# binaryspacebadgev1.net
KiCad netlist of a schematic drawn in EAGLE
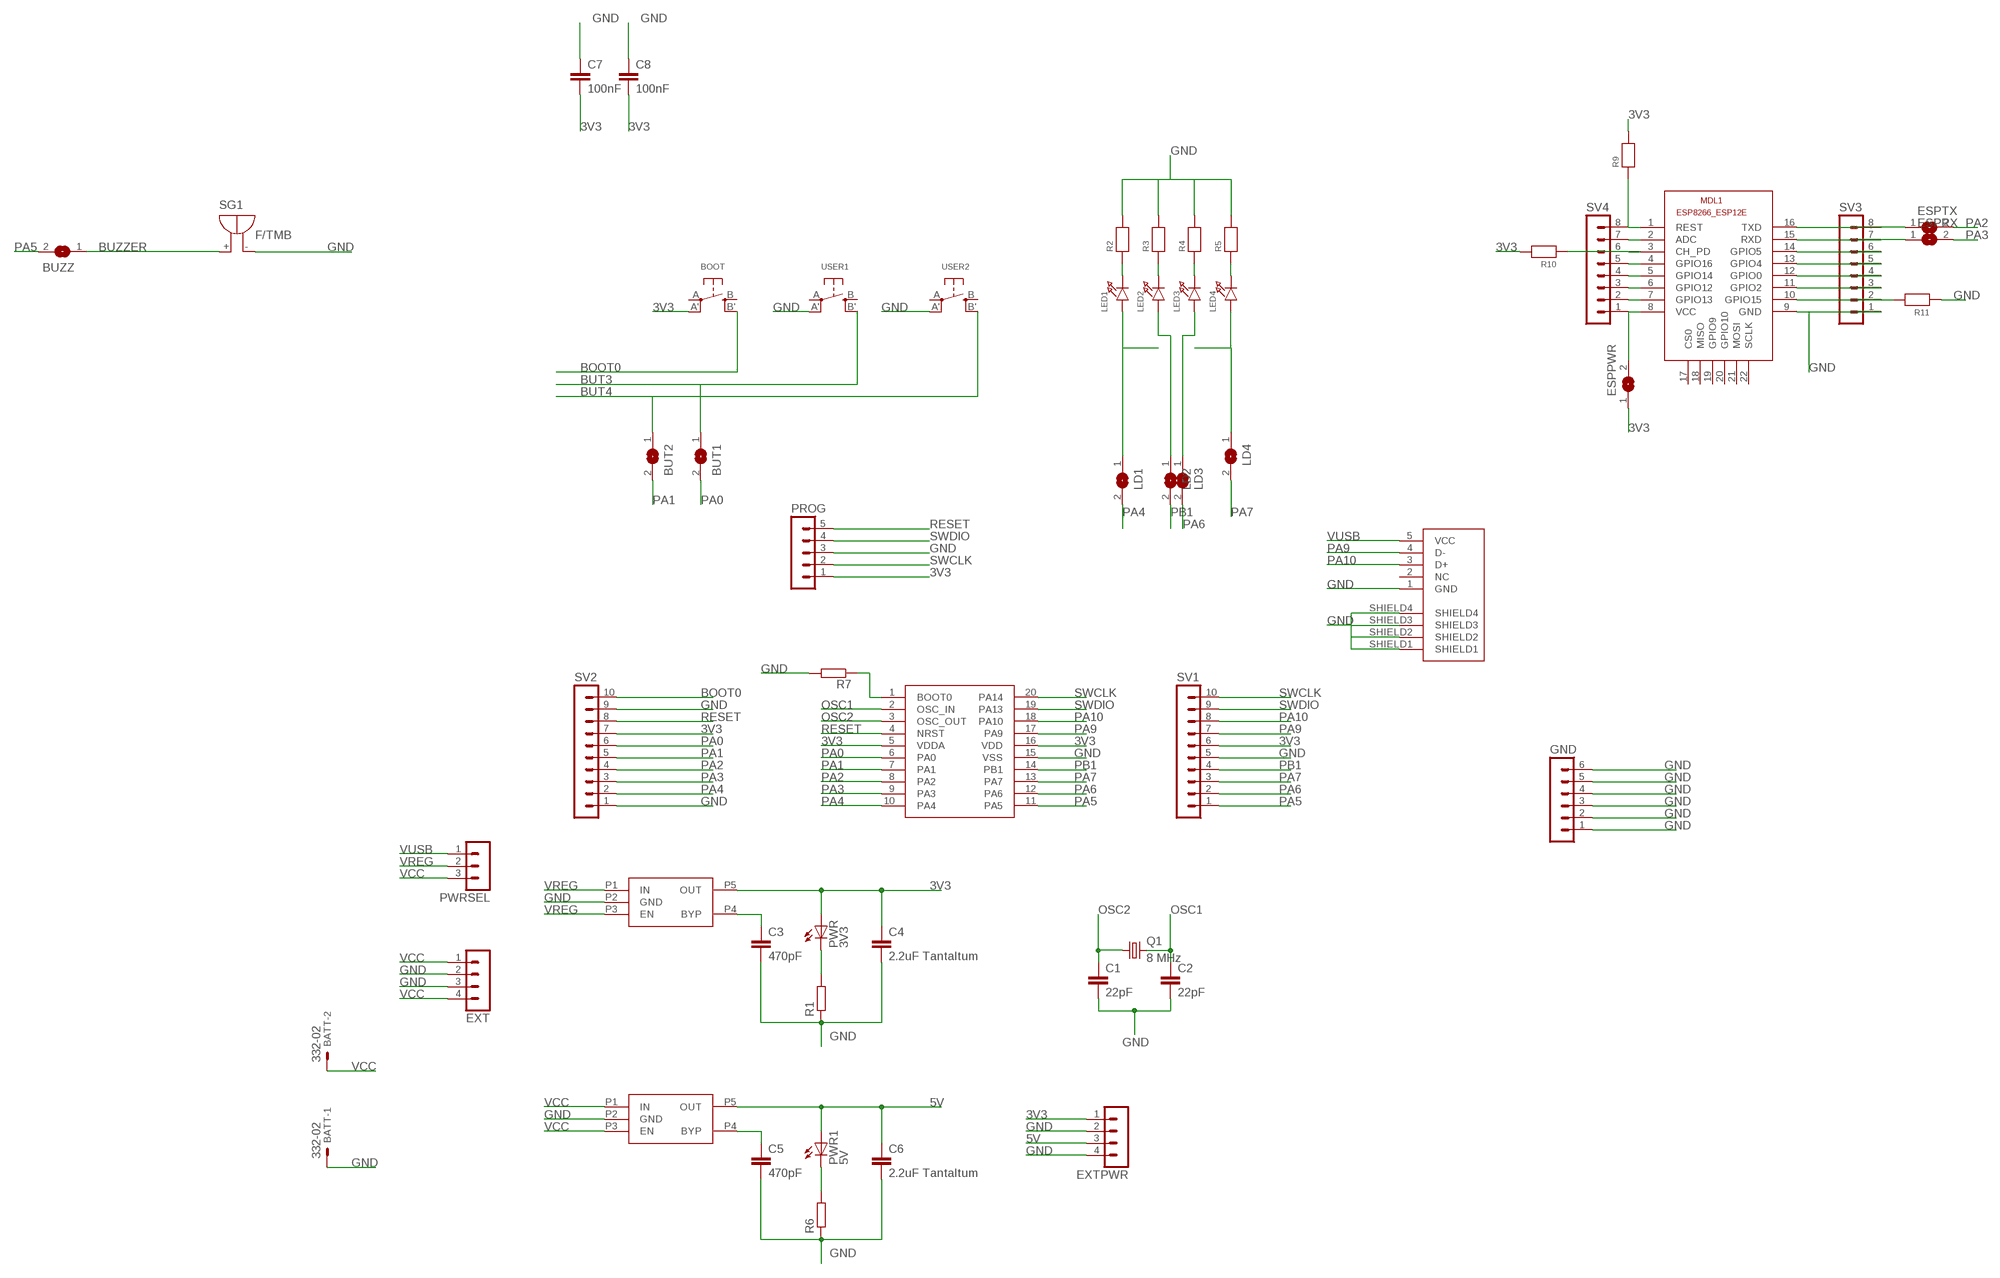
[diagram p0: schematic, sheet 1]

(export (version "E")
  (design (tool "Eeschema 10.0.6"))
  (components
    (comp (ref "BATT")
      (value "332-02")
      (footprint "eagle-import:332-02")
      (libsource (lib "eagle-import") (part "332-02"))
    )
    (comp (ref "BOOT")
      (value "SWITCH_TACT_SMT")
      (footprint "eagle-import:EVQ-Q2")
      (libsource (lib "eagle-import") (part "SWITCH_TACT_SMT"))
    )
    (comp (ref "BUT1")
      (value "SOLDERJUMPER")
      (footprint "eagle-import:SOLDERJUMPER_ARROW_NOPASTE")
      (libsource (lib "eagle-import") (part "SOLDERJUMPER"))
    )
    (comp (ref "BUT2")
      (value "SOLDERJUMPER")
      (footprint "eagle-import:SOLDERJUMPER_ARROW_NOPASTE")
      (libsource (lib "eagle-import") (part "SOLDERJUMPER"))
    )
    (comp (ref "BUZZ")
      (value "SOLDERJUMPER")
      (footprint "eagle-import:SOLDERJUMPER_ARROW_NOPASTE")
      (libsource (lib "eagle-import") (part "SOLDERJUMPER"))
    )
    (comp (ref "C1")
      (value "22pF")
      (footprint "eagle-import:C0603")
      (libsource (lib "eagle-import") (part "C-EUC0603"))
    )
    (comp (ref "C2")
      (value "22pF")
      (footprint "eagle-import:C0603")
      (libsource (lib "eagle-import") (part "C-EUC0603"))
    )
    (comp (ref "C3")
      (value "470pF")
      (footprint "eagle-import:C0603")
      (libsource (lib "eagle-import") (part "C-EUC0603"))
    )
    (comp (ref "C4")
      (value "2.2uF Tantaltum")
      (footprint "eagle-import:C0805")
      (libsource (lib "eagle-import") (part "C-EUC0805"))
    )
    (comp (ref "C5")
      (value "470pF")
      (footprint "eagle-import:C0603")
      (libsource (lib "eagle-import") (part "C-EUC0603"))
    )
    (comp (ref "C6")
      (value "2.2uF Tantaltum")
      (footprint "eagle-import:C0805")
      (libsource (lib "eagle-import") (part "C-EUC0805"))
    )
    (comp (ref "C7")
      (value "100nF")
      (footprint "eagle-import:C0603")
      (libsource (lib "eagle-import") (part "C-EUC0603"))
    )
    (comp (ref "C8")
      (value "100nF")
      (footprint "eagle-import:C0603")
      (libsource (lib "eagle-import") (part "C-EUC0603"))
    )
    (comp (ref "ESPPWR")
      (value "SOLDERJUMPER")
      (footprint "eagle-import:SOLDERJUMPER_ARROW_NOPASTE")
      (libsource (lib "eagle-import") (part "SOLDERJUMPER"))
    )
    (comp (ref "ESPRX")
      (value "SOLDERJUMPER")
      (footprint "eagle-import:SOLDERJUMPER_ARROW_NOPASTE")
      (libsource (lib "eagle-import") (part "SOLDERJUMPER"))
    )
    (comp (ref "ESPTX")
      (value "SOLDERJUMPER")
      (footprint "eagle-import:SOLDERJUMPER_ARROW_NOPASTE")
      (libsource (lib "eagle-import") (part "SOLDERJUMPER"))
    )
    (comp (ref "EXT")
      (value "MA04-1")
      (footprint "eagle-import:MA04-1")
      (libsource (lib "eagle-import") (part "MA04-1"))
    )
    (comp (ref "EXTPWR")
      (value "MA04-1")
      (footprint "eagle-import:MA04-1")
      (libsource (lib "eagle-import") (part "MA04-1"))
    )
    (comp (ref "GND")
      (value "MA06-1")
      (footprint "eagle-import:MA06-1")
      (libsource (lib "eagle-import") (part "MA06-1"))
    )
    (comp (ref "LD1")
      (value "SOLDERJUMPER")
      (footprint "eagle-import:SOLDERJUMPER_ARROW_NOPASTE")
      (libsource (lib "eagle-import") (part "SOLDERJUMPER"))
    )
    (comp (ref "LD2")
      (value "SOLDERJUMPER")
      (footprint "eagle-import:SOLDERJUMPER_ARROW_NOPASTE")
      (libsource (lib "eagle-import") (part "SOLDERJUMPER"))
    )
    (comp (ref "LD3")
      (value "SOLDERJUMPER")
      (footprint "eagle-import:SOLDERJUMPER_ARROW_NOPASTE")
      (libsource (lib "eagle-import") (part "SOLDERJUMPER"))
    )
    (comp (ref "LD4")
      (value "SOLDERJUMPER")
      (footprint "eagle-import:SOLDERJUMPER_ARROW_NOPASTE")
      (libsource (lib "eagle-import") (part "SOLDERJUMPER"))
    )
    (comp (ref "LED1")
      (value "LED0805")
      (footprint "eagle-import:CHIPLED_0805")
      (libsource (lib "eagle-import") (part "LED0805"))
    )
    (comp (ref "LED2")
      (value "LED0805")
      (footprint "eagle-import:CHIPLED_0805")
      (libsource (lib "eagle-import") (part "LED0805"))
    )
    (comp (ref "LED3")
      (value "LED0805")
      (footprint "eagle-import:CHIPLED_0805")
      (libsource (lib "eagle-import") (part "LED0805"))
    )
    (comp (ref "LED4")
      (value "LED0805")
      (footprint "eagle-import:CHIPLED_0805")
      (libsource (lib "eagle-import") (part "LED0805"))
    )
    (comp (ref "MDL1")
      (value "ESP8266-12EESP8266-ESP12E")
      (footprint "eagle-import:ESP8266-ESP12E")
      (libsource (lib "eagle-import") (part "ESP8266-12EESP8266-ESP12E"))
    )
    (comp (ref "PROG")
      (value "MA05-1")
      (footprint "eagle-import:MA05-1")
      (libsource (lib "eagle-import") (part "MA05-1"))
    )
    (comp (ref "PWR")
      (value "3V3")
      (footprint "eagle-import:SML0603")
      (libsource (lib "eagle-import") (part "LEDSML0603"))
    )
    (comp (ref "PWR1")
      (value "5V")
      (footprint "eagle-import:SML0603")
      (libsource (lib "eagle-import") (part "LEDSML0603"))
    )
    (comp (ref "PWRSEL")
      (value "MA03-1")
      (footprint "eagle-import:MA03-1")
      (libsource (lib "eagle-import") (part "MA03-1"))
    )
    (comp (ref "Q1")
      (value "8 MHz")
      (footprint "eagle-import:SM49")
      (libsource (lib "eagle-import") (part "CRYSTAL"))
    )
    (comp (ref "R1")
      (value "R-EU_R0603")
      (footprint "eagle-import:R0603")
      (libsource (lib "eagle-import") (part "R-EU_R0603"))
    )
    (comp (ref "R2")
      (value "RESISTOR0603")
      (footprint "eagle-import:0603")
      (libsource (lib "eagle-import") (part "RESISTOR0603"))
    )
    (comp (ref "R3")
      (value "RESISTOR0603")
      (footprint "eagle-import:0603")
      (libsource (lib "eagle-import") (part "RESISTOR0603"))
    )
    (comp (ref "R4")
      (value "RESISTOR0603")
      (footprint "eagle-import:0603")
      (libsource (lib "eagle-import") (part "RESISTOR0603"))
    )
    (comp (ref "R5")
      (value "RESISTOR0603")
      (footprint "eagle-import:0603")
      (libsource (lib "eagle-import") (part "RESISTOR0603"))
    )
    (comp (ref "R6")
      (value "R-EU_R0603")
      (footprint "eagle-import:R0603")
      (libsource (lib "eagle-import") (part "R-EU_R0603"))
    )
    (comp (ref "R7")
      (value "R-EU_R0603")
      (footprint "eagle-import:R0603")
      (libsource (lib "eagle-import") (part "R-EU_R0603"))
    )
    (comp (ref "R9")
      (value "RESISTOR0603")
      (footprint "eagle-import:0603")
      (libsource (lib "eagle-import") (part "RESISTOR0603"))
    )
    (comp (ref "R10")
      (value "RESISTOR0603")
      (footprint "eagle-import:0603")
      (libsource (lib "eagle-import") (part "RESISTOR0603"))
    )
    (comp (ref "R11")
      (value "RESISTOR0603")
      (footprint "eagle-import:0603")
      (libsource (lib "eagle-import") (part "RESISTOR0603"))
    )
    (comp (ref "SG1")
      (value "F/TMB")
      (footprint "eagle-import:F_TMB")
      (libsource (lib "eagle-import") (part "F/TMB"))
    )
    (comp (ref "SV1")
      (value "MA10-1")
      (footprint "eagle-import:MA10-1")
      (libsource (lib "eagle-import") (part "MA10-1"))
    )
    (comp (ref "SV2")
      (value "MA10-1")
      (footprint "eagle-import:MA10-1")
      (libsource (lib "eagle-import") (part "MA10-1"))
    )
    (comp (ref "SV3")
      (value "MA08-1")
      (footprint "eagle-import:MA08-1")
      (libsource (lib "eagle-import") (part "MA08-1"))
    )
    (comp (ref "SV4")
      (value "MA08-1")
      (footprint "eagle-import:MA08-1")
      (libsource (lib "eagle-import") (part "MA08-1"))
    )
    (comp (ref "U$1")
      (value "STM32F030X4792-5925")
      (footprint "eagle-import:TSSOP20")
      (libsource (lib "eagle-import") (part "STM32F030X4792-5925"))
    )
    (comp (ref "U$2")
      (value "MIC5219-X.XBM5MIC5219-3.3YM5TR")
      (footprint "eagle-import:SOT-23-5")
      (libsource (lib "eagle-import") (part "MIC5219-X.XBM5MIC5219-3.3YM5TR"))
    )
    (comp (ref "U$3")
      (value "USBSOCK_MINI_SMD")
      (footprint "eagle-import:USBSOCK_MINI_SMD")
      (libsource (lib "eagle-import") (part "USBSOCK_MINI_SMD"))
    )
    (comp (ref "U$4")
      (value "MIC5219-X.XBM5MIC5219-3.3YM5TR")
      (footprint "eagle-import:SOT-23-5")
      (libsource (lib "eagle-import") (part "MIC5219-X.XBM5MIC5219-3.3YM5TR"))
    )
    (comp (ref "USER1")
      (value "SWITCH_TACT_SMT")
      (footprint "eagle-import:EVQ-Q2")
      (libsource (lib "eagle-import") (part "SWITCH_TACT_SMT"))
    )
    (comp (ref "USER2")
      (value "SWITCH_TACT_SMT")
      (footprint "eagle-import:EVQ-Q2")
      (libsource (lib "eagle-import") (part "SWITCH_TACT_SMT"))
    )
  )
  (nets
    (net (code "1") (name "/3V3") (class "Default")
      (node (ref "BOOT") (pin "A'") (pinfunction "P1_A'") (pintype "passive"))
      (node (ref "C4") (pin "1") (pinfunction "1_1") (pintype "passive"))
      (node (ref "C7") (pin "2") (pinfunction "2_2") (pintype "passive"))
      (node (ref "C8") (pin "2") (pinfunction "2_2") (pintype "passive"))
      (node (ref "ESPPWR") (pin "1") (pinfunction "1_1") (pintype "passive"))
      (node (ref "EXTPWR") (pin "1") (pinfunction "1_1") (pintype "passive"))
      (node (ref "PROG") (pin "1") (pinfunction "1_1") (pintype "passive"))
      (node (ref "PWR") (pin "A") (pinfunction "A_A") (pintype "passive"))
      (node (ref "R10") (pin "2") (pinfunction "2_2") (pintype "passive"))
      (node (ref "R9") (pin "2") (pinfunction "2_2") (pintype "passive"))
      (node (ref "SV1") (pin "6") (pinfunction "6_6") (pintype "passive"))
      (node (ref "SV2") (pin "7") (pinfunction "7_7") (pintype "passive"))
      (node (ref "U$1") (pin "16") (pinfunction "VDD_16") (pintype "bidirectional"))
      (node (ref "U$1") (pin "5") (pinfunction "VDDA_5") (pintype "bidirectional"))
      (node (ref "U$2") (pin "P5") (pinfunction "OUT_P5") (pintype "bidirectional"))
    )
    (net (code "2") (name "/5V") (class "Default")
      (node (ref "C6") (pin "1") (pinfunction "1_1") (pintype "passive"))
      (node (ref "EXTPWR") (pin "3") (pinfunction "3_3") (pintype "passive"))
      (node (ref "PWR1") (pin "A") (pinfunction "A_A") (pintype "passive"))
      (node (ref "U$4") (pin "P5") (pinfunction "OUT_P5") (pintype "bidirectional"))
    )
    (net (code "3") (name "/BOOT0") (class "Default")
      (node (ref "BOOT") (pin "B'") (pinfunction "S1_B'") (pintype "passive"))
      (node (ref "R7") (pin "1") (pinfunction "1_1") (pintype "passive"))
      (node (ref "SV2") (pin "10") (pinfunction "10_10") (pintype "passive"))
      (node (ref "U$1") (pin "1") (pinfunction "BOOT0_1") (pintype "bidirectional"))
    )
    (net (code "4") (name "/BUT3") (class "Default")
      (node (ref "BUT1") (pin "1") (pinfunction "1_1") (pintype "passive"))
      (node (ref "USER1") (pin "B'") (pinfunction "S1_B'") (pintype "passive"))
    )
    (net (code "5") (name "/BUT4") (class "Default")
      (node (ref "BUT2") (pin "1") (pinfunction "1_1") (pintype "passive"))
      (node (ref "USER2") (pin "B'") (pinfunction "S1_B'") (pintype "passive"))
    )
    (net (code "6") (name "/BUZZER") (class "Default")
      (node (ref "BUZZ") (pin "1") (pinfunction "1_1") (pintype "passive"))
      (node (ref "SG1") (pin "+") (pinfunction "+_+") (pintype "passive"))
    )
    (net (code "7") (name "/GND") (class "Default")
      (node (ref "BATT") (pin "1") (pinfunction "S_1") (pintype "passive"))
      (node (ref "C1") (pin "2") (pinfunction "2_2") (pintype "passive"))
      (node (ref "C2") (pin "2") (pinfunction "2_2") (pintype "passive"))
      (node (ref "C3") (pin "2") (pinfunction "2_2") (pintype "passive"))
      (node (ref "C4") (pin "2") (pinfunction "2_2") (pintype "passive"))
      (node (ref "C5") (pin "2") (pinfunction "2_2") (pintype "passive"))
      (node (ref "C6") (pin "2") (pinfunction "2_2") (pintype "passive"))
      (node (ref "C7") (pin "1") (pinfunction "1_1") (pintype "passive"))
      (node (ref "C8") (pin "1") (pinfunction "1_1") (pintype "passive"))
      (node (ref "EXT") (pin "2") (pinfunction "2_2") (pintype "passive"))
      (node (ref "EXT") (pin "3") (pinfunction "3_3") (pintype "passive"))
      (node (ref "EXTPWR") (pin "2") (pinfunction "2_2") (pintype "passive"))
      (node (ref "EXTPWR") (pin "4") (pinfunction "4_4") (pintype "passive"))
      (node (ref "GND") (pin "1") (pinfunction "1_1") (pintype "passive"))
      (node (ref "GND") (pin "2") (pinfunction "2_2") (pintype "passive"))
      (node (ref "GND") (pin "3") (pinfunction "3_3") (pintype "passive"))
      (node (ref "GND") (pin "4") (pinfunction "4_4") (pintype "passive"))
      (node (ref "GND") (pin "5") (pinfunction "5_5") (pintype "passive"))
      (node (ref "GND") (pin "6") (pinfunction "6_6") (pintype "passive"))
      (node (ref "MDL1") (pin "9") (pinfunction "GND_9") (pintype "bidirectional"))
      (node (ref "PROG") (pin "3") (pinfunction "3_3") (pintype "passive"))
      (node (ref "R1") (pin "1") (pinfunction "1_1") (pintype "passive"))
      (node (ref "R11") (pin "1") (pinfunction "1_1") (pintype "passive"))
      (node (ref "R2") (pin "2") (pinfunction "2_2") (pintype "passive"))
      (node (ref "R3") (pin "2") (pinfunction "2_2") (pintype "passive"))
      (node (ref "R4") (pin "2") (pinfunction "2_2") (pintype "passive"))
      (node (ref "R5") (pin "2") (pinfunction "2_2") (pintype "passive"))
      (node (ref "R6") (pin "1") (pinfunction "1_1") (pintype "passive"))
      (node (ref "R7") (pin "2") (pinfunction "2_2") (pintype "passive"))
      (node (ref "SG1") (pin "-") (pinfunction "-_-") (pintype "passive"))
      (node (ref "SV1") (pin "5") (pinfunction "5_5") (pintype "passive"))
      (node (ref "SV2") (pin "1") (pinfunction "1_1") (pintype "passive"))
      (node (ref "SV2") (pin "9") (pinfunction "9_9") (pintype "passive"))
      (node (ref "SV3") (pin "1") (pinfunction "1_1") (pintype "passive"))
      (node (ref "U$1") (pin "15") (pinfunction "VSS_15") (pintype "bidirectional"))
      (node (ref "U$2") (pin "P2") (pinfunction "GND_P2") (pintype "bidirectional"))
      (node (ref "U$3") (pin "1") (pinfunction "GND_1") (pintype "bidirectional"))
      (node (ref "U$3") (pin "SHIELD1") (pinfunction "SHIELD1_SHIELD1") (pintype "bidirectional"))
      (node (ref "U$3") (pin "SHIELD2") (pinfunction "SHIELD2_SHIELD2") (pintype "bidirectional"))
      (node (ref "U$3") (pin "SHIELD3") (pinfunction "SHIELD3_SHIELD3") (pintype "bidirectional"))
      (node (ref "U$3") (pin "SHIELD4") (pinfunction "SHIELD4_SHIELD4") (pintype "bidirectional"))
      (node (ref "U$4") (pin "P2") (pinfunction "GND_P2") (pintype "bidirectional"))
      (node (ref "USER1") (pin "A'") (pinfunction "P1_A'") (pintype "passive"))
      (node (ref "USER2") (pin "A'") (pinfunction "P1_A'") (pintype "passive"))
    )
    (net (code "8") (name "/OSC1") (class "Default")
      (node (ref "C2") (pin "1") (pinfunction "1_1") (pintype "passive"))
      (node (ref "Q1") (pin "2") (pinfunction "2_2") (pintype "passive"))
      (node (ref "U$1") (pin "2") (pinfunction "OSC_IN_2") (pintype "bidirectional"))
    )
    (net (code "9") (name "/OSC2") (class "Default")
      (node (ref "C1") (pin "1") (pinfunction "1_1") (pintype "passive"))
      (node (ref "Q1") (pin "1") (pinfunction "1_1") (pintype "passive"))
      (node (ref "U$1") (pin "3") (pinfunction "OSC_OUT_3") (pintype "bidirectional"))
    )
    (net (code "10") (name "/PA0") (class "Default")
      (node (ref "BUT1") (pin "2") (pinfunction "2_2") (pintype "passive"))
      (node (ref "SV2") (pin "6") (pinfunction "6_6") (pintype "passive"))
      (node (ref "U$1") (pin "6") (pinfunction "PA0_6") (pintype "bidirectional"))
    )
    (net (code "11") (name "/PA1") (class "Default")
      (node (ref "BUT2") (pin "2") (pinfunction "2_2") (pintype "passive"))
      (node (ref "SV2") (pin "5") (pinfunction "5_5") (pintype "passive"))
      (node (ref "U$1") (pin "7") (pinfunction "PA1_7") (pintype "bidirectional"))
    )
    (net (code "12") (name "/PA2") (class "Default")
      (node (ref "ESPTX") (pin "2") (pinfunction "2_2") (pintype "passive"))
      (node (ref "SV2") (pin "4") (pinfunction "4_4") (pintype "passive"))
      (node (ref "U$1") (pin "8") (pinfunction "PA2_8") (pintype "bidirectional"))
    )
    (net (code "13") (name "/PA3") (class "Default")
      (node (ref "ESPRX") (pin "2") (pinfunction "2_2") (pintype "passive"))
      (node (ref "SV2") (pin "3") (pinfunction "3_3") (pintype "passive"))
      (node (ref "U$1") (pin "9") (pinfunction "PA3_9") (pintype "bidirectional"))
    )
    (net (code "14") (name "/PA4") (class "Default")
      (node (ref "LD1") (pin "2") (pinfunction "2_2") (pintype "passive"))
      (node (ref "SV2") (pin "2") (pinfunction "2_2") (pintype "passive"))
      (node (ref "U$1") (pin "10") (pinfunction "PA4_10") (pintype "bidirectional"))
    )
    (net (code "15") (name "/PA5") (class "Default")
      (node (ref "BUZZ") (pin "2") (pinfunction "2_2") (pintype "passive"))
      (node (ref "SV1") (pin "1") (pinfunction "1_1") (pintype "passive"))
      (node (ref "U$1") (pin "11") (pinfunction "PA5_11") (pintype "bidirectional"))
    )
    (net (code "16") (name "/PA6") (class "Default")
      (node (ref "LD3") (pin "2") (pinfunction "2_2") (pintype "passive"))
      (node (ref "SV1") (pin "2") (pinfunction "2_2") (pintype "passive"))
      (node (ref "U$1") (pin "12") (pinfunction "PA6_12") (pintype "bidirectional"))
    )
    (net (code "17") (name "/PA7") (class "Default")
      (node (ref "LD4") (pin "2") (pinfunction "2_2") (pintype "passive"))
      (node (ref "SV1") (pin "3") (pinfunction "3_3") (pintype "passive"))
      (node (ref "U$1") (pin "13") (pinfunction "PA7_13") (pintype "bidirectional"))
    )
    (net (code "18") (name "/PA9") (class "Default")
      (node (ref "SV1") (pin "7") (pinfunction "7_7") (pintype "passive"))
      (node (ref "U$1") (pin "17") (pinfunction "PA9_17") (pintype "bidirectional"))
      (node (ref "U$3") (pin "4") (pinfunction "D-_4") (pintype "bidirectional"))
    )
    (net (code "19") (name "/PA10") (class "Default")
      (node (ref "SV1") (pin "8") (pinfunction "8_8") (pintype "passive"))
      (node (ref "U$1") (pin "18") (pinfunction "PA10_18") (pintype "bidirectional"))
      (node (ref "U$3") (pin "3") (pinfunction "D+_3") (pintype "bidirectional"))
    )
    (net (code "20") (name "/PB1") (class "Default")
      (node (ref "LD2") (pin "2") (pinfunction "2_2") (pintype "passive"))
      (node (ref "SV1") (pin "4") (pinfunction "4_4") (pintype "passive"))
      (node (ref "U$1") (pin "14") (pinfunction "PB1_14") (pintype "bidirectional"))
    )
    (net (code "21") (name "/RESET") (class "Default")
      (node (ref "PROG") (pin "5") (pinfunction "5_5") (pintype "passive"))
      (node (ref "SV2") (pin "8") (pinfunction "8_8") (pintype "passive"))
      (node (ref "U$1") (pin "4") (pinfunction "NRST_4") (pintype "bidirectional"))
    )
    (net (code "22") (name "/SWCLK") (class "Default")
      (node (ref "PROG") (pin "2") (pinfunction "2_2") (pintype "passive"))
      (node (ref "SV1") (pin "10") (pinfunction "10_10") (pintype "passive"))
      (node (ref "U$1") (pin "20") (pinfunction "PA14_20") (pintype "bidirectional"))
    )
    (net (code "23") (name "/SWDIO") (class "Default")
      (node (ref "PROG") (pin "4") (pinfunction "4_4") (pintype "passive"))
      (node (ref "SV1") (pin "9") (pinfunction "9_9") (pintype "passive"))
      (node (ref "U$1") (pin "19") (pinfunction "PA13_19") (pintype "bidirectional"))
    )
    (net (code "24") (name "/VCC") (class "Default")
      (node (ref "BATT") (pin "2") (pinfunction "S_2") (pintype "passive"))
      (node (ref "EXT") (pin "1") (pinfunction "1_1") (pintype "passive"))
      (node (ref "EXT") (pin "4") (pinfunction "4_4") (pintype "passive"))
      (node (ref "PWRSEL") (pin "3") (pinfunction "3_3") (pintype "passive"))
      (node (ref "U$4") (pin "P1") (pinfunction "IN_P1") (pintype "bidirectional"))
      (node (ref "U$4") (pin "P3") (pinfunction "EN_P3") (pintype "bidirectional"))
    )
    (net (code "25") (name "/VREG") (class "Default")
      (node (ref "PWRSEL") (pin "2") (pinfunction "2_2") (pintype "passive"))
      (node (ref "U$2") (pin "P1") (pinfunction "IN_P1") (pintype "bidirectional"))
      (node (ref "U$2") (pin "P3") (pinfunction "EN_P3") (pintype "bidirectional"))
    )
    (net (code "26") (name "/VUSB") (class "Default")
      (node (ref "PWRSEL") (pin "1") (pinfunction "1_1") (pintype "passive"))
      (node (ref "U$3") (pin "5") (pinfunction "VCC_5") (pintype "bidirectional"))
    )
    (net (code "27") (name "Net-(LD1-Pad1)") (class "Default")
      (node (ref "LD1") (pin "1") (pinfunction "1_1") (pintype "passive"))
      (node (ref "LED1") (pin "A") (pinfunction "A_A") (pintype "passive"))
    )
    (net (code "28") (name "Net-(LD2-Pad1)") (class "Default")
      (node (ref "LD2") (pin "1") (pinfunction "1_1") (pintype "passive"))
      (node (ref "LED2") (pin "A") (pinfunction "A_A") (pintype "passive"))
    )
    (net (code "29") (name "Net-(LD3-Pad1)") (class "Default")
      (node (ref "LD3") (pin "1") (pinfunction "1_1") (pintype "passive"))
      (node (ref "LED3") (pin "A") (pinfunction "A_A") (pintype "passive"))
    )
    (net (code "30") (name "Net-(LD4-Pad1)") (class "Default")
      (node (ref "LD4") (pin "1") (pinfunction "1_1") (pintype "passive"))
      (node (ref "LED4") (pin "A") (pinfunction "A_A") (pintype "passive"))
    )
    (net (code "31") (name "Net-(LED1-PadC)") (class "Default")
      (node (ref "LED1") (pin "C") (pinfunction "C_C") (pintype "passive"))
      (node (ref "R2") (pin "1") (pinfunction "1_1") (pintype "passive"))
    )
    (net (code "32") (name "Net-(LED2-PadC)") (class "Default")
      (node (ref "LED2") (pin "C") (pinfunction "C_C") (pintype "passive"))
      (node (ref "R3") (pin "1") (pinfunction "1_1") (pintype "passive"))
    )
    (net (code "33") (name "Net-(LED3-PadC)") (class "Default")
      (node (ref "LED3") (pin "C") (pinfunction "C_C") (pintype "passive"))
      (node (ref "R4") (pin "1") (pinfunction "1_1") (pintype "passive"))
    )
    (net (code "34") (name "Net-(LED4-PadC)") (class "Default")
      (node (ref "LED4") (pin "C") (pinfunction "C_C") (pintype "passive"))
      (node (ref "R5") (pin "1") (pinfunction "1_1") (pintype "passive"))
    )
    (net (code "35") (name "Net-(MDL1-ADC)") (class "Default")
      (node (ref "MDL1") (pin "2") (pinfunction "ADC_2") (pintype "bidirectional"))
      (node (ref "SV4") (pin "7") (pinfunction "7_7") (pintype "passive"))
    )
    (net (code "36") (name "Net-(MDL1-CH_PD)") (class "Default")
      (node (ref "MDL1") (pin "3") (pinfunction "CH_PD_3") (pintype "bidirectional"))
      (node (ref "R10") (pin "1") (pinfunction "1_1") (pintype "passive"))
      (node (ref "SV4") (pin "6") (pinfunction "6_6") (pintype "passive"))
    )
    (net (code "37") (name "Net-(MDL1-GPIO0)") (class "Default")
      (node (ref "MDL1") (pin "12") (pinfunction "GPIO0_12") (pintype "bidirectional"))
      (node (ref "SV3") (pin "4") (pinfunction "4_4") (pintype "passive"))
    )
    (net (code "38") (name "Net-(MDL1-GPIO2)") (class "Default")
      (node (ref "MDL1") (pin "11") (pinfunction "GPIO2_11") (pintype "bidirectional"))
      (node (ref "SV3") (pin "3") (pinfunction "3_3") (pintype "passive"))
    )
    (net (code "39") (name "Net-(MDL1-GPIO4)") (class "Default")
      (node (ref "MDL1") (pin "13") (pinfunction "GPIO4_13") (pintype "bidirectional"))
      (node (ref "SV3") (pin "5") (pinfunction "5_5") (pintype "passive"))
    )
    (net (code "40") (name "Net-(MDL1-GPIO5)") (class "Default")
      (node (ref "MDL1") (pin "14") (pinfunction "GPIO5_14") (pintype "bidirectional"))
      (node (ref "SV3") (pin "6") (pinfunction "6_6") (pintype "passive"))
    )
    (net (code "41") (name "Net-(MDL1-GPIO12)") (class "Default")
      (node (ref "MDL1") (pin "6") (pinfunction "GPIO12_6") (pintype "bidirectional"))
      (node (ref "SV4") (pin "3") (pinfunction "3_3") (pintype "passive"))
    )
    (net (code "42") (name "Net-(MDL1-GPIO13)") (class "Default")
      (node (ref "MDL1") (pin "7") (pinfunction "GPIO13_7") (pintype "bidirectional"))
      (node (ref "SV4") (pin "2") (pinfunction "2_2") (pintype "passive"))
    )
    (net (code "43") (name "Net-(MDL1-GPIO14)") (class "Default")
      (node (ref "MDL1") (pin "5") (pinfunction "GPIO14_5") (pintype "bidirectional"))
      (node (ref "SV4") (pin "4") (pinfunction "4_4") (pintype "passive"))
    )
    (net (code "44") (name "Net-(MDL1-GPIO15)") (class "Default")
      (node (ref "MDL1") (pin "10") (pinfunction "GPIO15_10") (pintype "bidirectional"))
      (node (ref "R11") (pin "2") (pinfunction "2_2") (pintype "passive"))
      (node (ref "SV3") (pin "2") (pinfunction "2_2") (pintype "passive"))
    )
    (net (code "45") (name "Net-(MDL1-GPIO16)") (class "Default")
      (node (ref "MDL1") (pin "4") (pinfunction "GPIO16_4") (pintype "bidirectional"))
      (node (ref "SV4") (pin "5") (pinfunction "5_5") (pintype "passive"))
    )
    (net (code "46") (name "Net-(MDL1-REST)") (class "Default")
      (node (ref "MDL1") (pin "1") (pinfunction "REST_1") (pintype "bidirectional"))
      (node (ref "R9") (pin "1") (pinfunction "1_1") (pintype "passive"))
      (node (ref "SV4") (pin "8") (pinfunction "8_8") (pintype "passive"))
    )
    (net (code "47") (name "Net-(MDL1-RXD)") (class "Default")
      (node (ref "ESPRX") (pin "1") (pinfunction "1_1") (pintype "passive"))
      (node (ref "MDL1") (pin "15") (pinfunction "RXD_15") (pintype "bidirectional"))
      (node (ref "SV3") (pin "7") (pinfunction "7_7") (pintype "passive"))
    )
    (net (code "48") (name "Net-(MDL1-TXD)") (class "Default")
      (node (ref "ESPTX") (pin "1") (pinfunction "1_1") (pintype "passive"))
      (node (ref "MDL1") (pin "16") (pinfunction "TXD_16") (pintype "bidirectional"))
      (node (ref "SV3") (pin "8") (pinfunction "8_8") (pintype "passive"))
    )
    (net (code "49") (name "Net-(MDL1-VCC)") (class "Default")
      (node (ref "ESPPWR") (pin "2") (pinfunction "2_2") (pintype "passive"))
      (node (ref "MDL1") (pin "8") (pinfunction "VCC_8") (pintype "bidirectional"))
      (node (ref "SV4") (pin "1") (pinfunction "1_1") (pintype "passive"))
    )
    (net (code "50") (name "Net-(PWR-PadC)") (class "Default")
      (node (ref "PWR") (pin "C") (pinfunction "C_C") (pintype "passive"))
      (node (ref "R1") (pin "2") (pinfunction "2_2") (pintype "passive"))
    )
    (net (code "51") (name "Net-(PWR1-PadC)") (class "Default")
      (node (ref "PWR1") (pin "C") (pinfunction "C_C") (pintype "passive"))
      (node (ref "R6") (pin "2") (pinfunction "2_2") (pintype "passive"))
    )
    (net (code "52") (name "Net-(U$2-BYP)") (class "Default")
      (node (ref "C3") (pin "1") (pinfunction "1_1") (pintype "passive"))
      (node (ref "U$2") (pin "P4") (pinfunction "BYP_P4") (pintype "bidirectional"))
    )
    (net (code "53") (name "Net-(U$4-BYP)") (class "Default")
      (node (ref "C5") (pin "1") (pinfunction "1_1") (pintype "passive"))
      (node (ref "U$4") (pin "P4") (pinfunction "BYP_P4") (pintype "bidirectional"))
    )
    (net (code "54") (name "unconnected-(BOOT-P-PadA)") (class "Default")
      (node (ref "BOOT") (pin "A") (pinfunction "P_A") (pintype "passive"))
    )
    (net (code "55") (name "unconnected-(BOOT-S-PadB)") (class "Default")
      (node (ref "BOOT") (pin "B") (pinfunction "S_B") (pintype "passive"))
    )
    (net (code "56") (name "unconnected-(MDL1-CS0-Pad17)") (class "Default")
      (node (ref "MDL1") (pin "17") (pinfunction "CS0_17") (pintype "bidirectional"))
    )
    (net (code "57") (name "unconnected-(MDL1-GPIO9-Pad19)") (class "Default")
      (node (ref "MDL1") (pin "19") (pinfunction "GPIO9_19") (pintype "bidirectional"))
    )
    (net (code "58") (name "unconnected-(MDL1-GPIO10-Pad20)") (class "Default")
      (node (ref "MDL1") (pin "20") (pinfunction "GPIO10_20") (pintype "bidirectional"))
    )
    (net (code "59") (name "unconnected-(MDL1-MISO-Pad18)") (class "Default")
      (node (ref "MDL1") (pin "18") (pinfunction "MISO_18") (pintype "bidirectional"))
    )
    (net (code "60") (name "unconnected-(MDL1-MOSI-Pad21)") (class "Default")
      (node (ref "MDL1") (pin "21") (pinfunction "MOSI_21") (pintype "bidirectional"))
    )
    (net (code "61") (name "unconnected-(MDL1-SCLK-Pad22)") (class "Default")
      (node (ref "MDL1") (pin "22") (pinfunction "SCLK_22") (pintype "bidirectional"))
    )
    (net (code "62") (name "unconnected-(U$3-NC-Pad2)") (class "Default")
      (node (ref "U$3") (pin "2") (pinfunction "NC_2") (pintype "bidirectional"))
    )
    (net (code "63") (name "unconnected-(USER1-P-PadA)") (class "Default")
      (node (ref "USER1") (pin "A") (pinfunction "P_A") (pintype "passive"))
    )
    (net (code "64") (name "unconnected-(USER1-S-PadB)") (class "Default")
      (node (ref "USER1") (pin "B") (pinfunction "S_B") (pintype "passive"))
    )
    (net (code "65") (name "unconnected-(USER2-P-PadA)") (class "Default")
      (node (ref "USER2") (pin "A") (pinfunction "P_A") (pintype "passive"))
    )
    (net (code "66") (name "unconnected-(USER2-S-PadB)") (class "Default")
      (node (ref "USER2") (pin "B") (pinfunction "S_B") (pintype "passive"))
    )
  )
)
